# transmission_end_copy-1.net
KiCad netlist of a schematic drawn in EAGLE
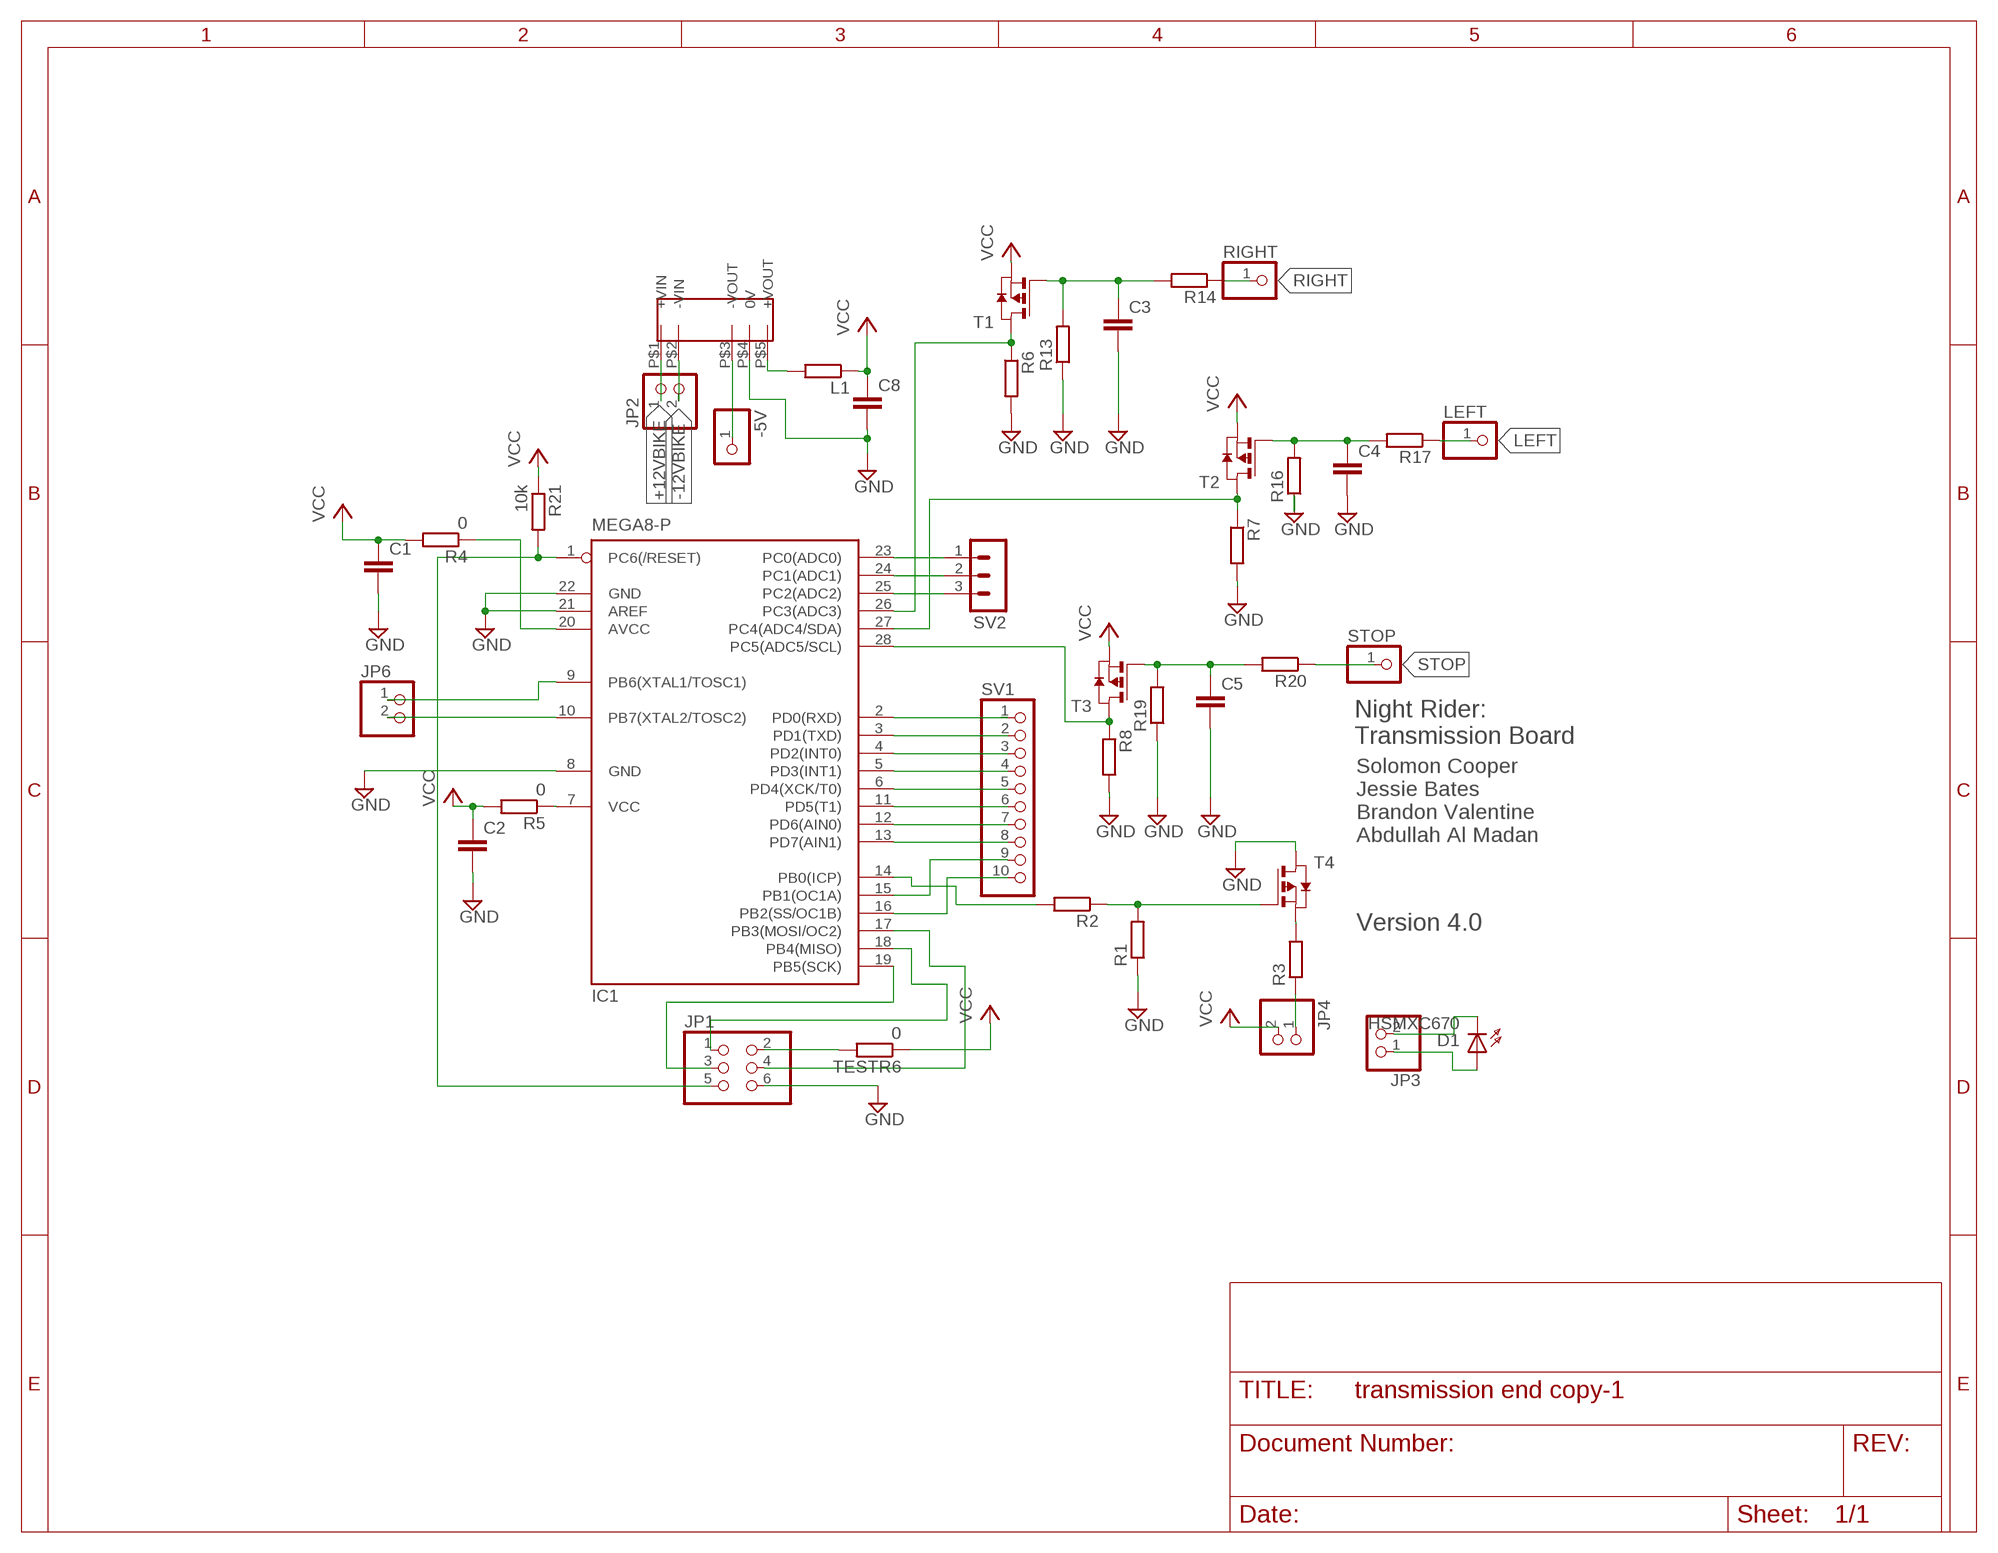
[diagram p0: schematic, sheet 1]

(export (version "E")
  (design (tool "Eeschema 10.0.6"))
  (components
    (comp (ref "-5V")
      (value "PINHD-1X1")
      (footprint "eagle-import:1X01")
      (libsource (lib "eagle-import") (part "PINHD-1X1"))
    )
    (comp (ref "C1")
      (value "C-EUC0805")
      (footprint "eagle-import:C0805")
      (libsource (lib "eagle-import") (part "C-EUC0805"))
    )
    (comp (ref "C2")
      (value "C-EUC0805")
      (footprint "eagle-import:C0805")
      (libsource (lib "eagle-import") (part "C-EUC0805"))
    )
    (comp (ref "C3")
      (value "C-EUC0805")
      (footprint "eagle-import:C0805")
      (libsource (lib "eagle-import") (part "C-EUC0805"))
    )
    (comp (ref "C4")
      (value "C-EUC0805")
      (footprint "eagle-import:C0805")
      (libsource (lib "eagle-import") (part "C-EUC0805"))
    )
    (comp (ref "C5")
      (value "C-EUC0805")
      (footprint "eagle-import:C0805")
      (libsource (lib "eagle-import") (part "C-EUC0805"))
    )
    (comp (ref "C8")
      (value "C-EUC0805")
      (footprint "eagle-import:C0805")
      (libsource (lib "eagle-import") (part "C-EUC0805"))
    )
    (comp (ref "D1")
      (value "HSMXC670")
      (footprint "eagle-import:HSMXC670")
      (fields (field (name "OC_FARNELL") "unknown") (field (name "OC_NEWARK") "unknown"))
      (libsource (lib "eagle-import") (part "HSMXC670"))
    )
    (comp (ref "IC1")
      (value "MEGA8-P")
      (footprint "eagle-import:DIL28-3")
      (libsource (lib "eagle-import") (part "MEGA8-P"))
    )
    (comp (ref "JP1")
      (value "PINHD-2X3")
      (footprint "eagle-import:2X03")
      (libsource (lib "eagle-import") (part "PINHD-2X3"))
    )
    (comp (ref "JP2")
      (value "PINHD-1X2")
      (footprint "eagle-import:1X02")
      (libsource (lib "eagle-import") (part "PINHD-1X2"))
    )
    (comp (ref "JP3")
      (value "PINHD-1X2")
      (footprint "eagle-import:1X02")
      (libsource (lib "eagle-import") (part "PINHD-1X2"))
    )
    (comp (ref "JP4")
      (value "PINHD-1X2")
      (footprint "eagle-import:1X02")
      (libsource (lib "eagle-import") (part "PINHD-1X2"))
    )
    (comp (ref "JP6")
      (value "PINHD-1X2")
      (footprint "eagle-import:1X02")
      (libsource (lib "eagle-import") (part "PINHD-1X2"))
    )
    (comp (ref "L1")
      (value "R-EU_M0805")
      (footprint "eagle-import:M0805")
      (libsource (lib "eagle-import") (part "R-EU_M0805"))
    )
    (comp (ref "LEFT")
      (value "PINHD-1X1")
      (footprint "eagle-import:1X01")
      (libsource (lib "eagle-import") (part "PINHD-1X1"))
    )
    (comp (ref "R1")
      (value "R-EU_M0805")
      (footprint "eagle-import:M0805")
      (libsource (lib "eagle-import") (part "R-EU_M0805"))
    )
    (comp (ref "R2")
      (value "R-EU_M0805")
      (footprint "eagle-import:M0805")
      (libsource (lib "eagle-import") (part "R-EU_M0805"))
    )
    (comp (ref "R3")
      (value "R-EU_M0805")
      (footprint "eagle-import:M0805")
      (libsource (lib "eagle-import") (part "R-EU_M0805"))
    )
    (comp (ref "R4")
      (value "0")
      (footprint "eagle-import:M0805")
      (libsource (lib "eagle-import") (part "R-EU_M0805"))
    )
    (comp (ref "R5")
      (value "0")
      (footprint "eagle-import:M0805")
      (libsource (lib "eagle-import") (part "R-EU_M0805"))
    )
    (comp (ref "R6")
      (value "R-EU_M0805")
      (footprint "eagle-import:M0805")
      (libsource (lib "eagle-import") (part "R-EU_M0805"))
    )
    (comp (ref "R7")
      (value "R-EU_M0805")
      (footprint "eagle-import:M0805")
      (libsource (lib "eagle-import") (part "R-EU_M0805"))
    )
    (comp (ref "R8")
      (value "R-EU_M0805")
      (footprint "eagle-import:M0805")
      (libsource (lib "eagle-import") (part "R-EU_M0805"))
    )
    (comp (ref "R13")
      (value "R-EU_M0805")
      (footprint "eagle-import:M0805")
      (libsource (lib "eagle-import") (part "R-EU_M0805"))
    )
    (comp (ref "R14")
      (value "R-EU_M0805")
      (footprint "eagle-import:M0805")
      (libsource (lib "eagle-import") (part "R-EU_M0805"))
    )
    (comp (ref "R16")
      (value "R-EU_M0805")
      (footprint "eagle-import:M0805")
      (libsource (lib "eagle-import") (part "R-EU_M0805"))
    )
    (comp (ref "R17")
      (value "R-EU_M0805")
      (footprint "eagle-import:M0805")
      (libsource (lib "eagle-import") (part "R-EU_M0805"))
    )
    (comp (ref "R19")
      (value "R-EU_M0805")
      (footprint "eagle-import:M0805")
      (libsource (lib "eagle-import") (part "R-EU_M0805"))
    )
    (comp (ref "R20")
      (value "R-EU_M0805")
      (footprint "eagle-import:M0805")
      (libsource (lib "eagle-import") (part "R-EU_M0805"))
    )
    (comp (ref "R21")
      (value "10k")
      (footprint "eagle-import:M0805")
      (libsource (lib "eagle-import") (part "R-EU_M0805"))
    )
    (comp (ref "RIGHT")
      (value "PINHD-1X1")
      (footprint "eagle-import:1X01")
      (libsource (lib "eagle-import") (part "PINHD-1X1"))
    )
    (comp (ref "STOP")
      (value "PINHD-1X1")
      (footprint "eagle-import:1X01")
      (libsource (lib "eagle-import") (part "PINHD-1X1"))
    )
    (comp (ref "SV1")
      (value "PINHD-1X10")
      (footprint "eagle-import:1X10")
      (libsource (lib "eagle-import") (part "PINHD-1X10"))
    )
    (comp (ref "SV2")
      (value "MA03-1")
      (footprint "eagle-import:MA03-1")
      (libsource (lib "eagle-import") (part "MA03-1"))
    )
    (comp (ref "T1")
      (value "PMOSSOT23")
      (footprint "eagle-import:SOT-23")
      (fields (field (name "OC_FARNELL") "unknown") (field (name "OC_NEWARK") "unknown"))
      (libsource (lib "eagle-import") (part "PMOSSOT23"))
    )
    (comp (ref "T2")
      (value "PMOSSOT23")
      (footprint "eagle-import:SOT-23")
      (libsource (lib "eagle-import") (part "PMOSSOT23"))
    )
    (comp (ref "T3")
      (value "PMOSSOT23")
      (footprint "eagle-import:SOT-23")
      (libsource (lib "eagle-import") (part "PMOSSOT23"))
    )
    (comp (ref "T4")
      (value "PMOSSOT23")
      (footprint "eagle-import:SOT-23")
      (fields (field (name "OC_FARNELL") "unknown") (field (name "OC_NEWARK") "unknown"))
      (libsource (lib "eagle-import") (part "PMOSSOT23"))
    )
    (comp (ref "TESTR6")
      (value "0")
      (footprint "eagle-import:M0805")
      (libsource (lib "eagle-import") (part "R-EU_M0805"))
    )
    (comp (ref "U$1")
      (value "NKA1205SC")
      (footprint "eagle-import:NKA1205SC")
      (libsource (lib "eagle-import") (part "NKA1205SC"))
    )
  )
  (nets
    (net (code "1") (name "+12VBIKE") (class "Default")
      (node (ref "JP2") (pin "1") (pinfunction "1_1") (pintype "passive"))
      (node (ref "U$1") (pin "P$1") (pinfunction "+VIN_P$1") (pintype "bidirectional"))
    )
    (net (code "2") (name "-12VBIKE") (class "Default")
      (node (ref "JP2") (pin "2") (pinfunction "2_2") (pintype "passive"))
      (node (ref "U$1") (pin "P$2") (pinfunction "-VIN_P$2") (pintype "bidirectional"))
    )
    (net (code "3") (name "GND") (class "Default")
      (node (ref "C1") (pin "2") (pinfunction "2_2") (pintype "passive"))
      (node (ref "C2") (pin "2") (pinfunction "2_2") (pintype "passive"))
      (node (ref "C3") (pin "2") (pinfunction "2_2") (pintype "passive"))
      (node (ref "C4") (pin "2") (pinfunction "2_2") (pintype "passive"))
      (node (ref "C5") (pin "2") (pinfunction "2_2") (pintype "passive"))
      (node (ref "C8") (pin "2") (pinfunction "2_2") (pintype "passive"))
      (node (ref "IC1") (pin "21") (pinfunction "AREF_21") (pintype "passive"))
      (node (ref "IC1") (pin "22") (pinfunction "GND_22") (pintype "power_in"))
      (node (ref "IC1") (pin "8") (pinfunction "GND_8") (pintype "power_in"))
      (node (ref "JP1") (pin "6") (pinfunction "6_6") (pintype "passive"))
      (node (ref "R1") (pin "1") (pinfunction "1_1") (pintype "passive"))
      (node (ref "R13") (pin "1") (pinfunction "1_1") (pintype "passive"))
      (node (ref "R16") (pin "1") (pinfunction "1_1") (pintype "passive"))
      (node (ref "R19") (pin "1") (pinfunction "1_1") (pintype "passive"))
      (node (ref "R6") (pin "2") (pinfunction "2_2") (pintype "passive"))
      (node (ref "R7") (pin "2") (pinfunction "2_2") (pintype "passive"))
      (node (ref "R8") (pin "2") (pinfunction "2_2") (pintype "passive"))
      (node (ref "T4") (pin "1") (pinfunction "D_1") (pintype "passive"))
      (node (ref "U$1") (pin "P$4") (pinfunction "0V_P$4") (pintype "bidirectional"))
    )
    (net (code "4") (name "LEFT") (class "Default")
      (node (ref "LEFT") (pin "1") (pinfunction "1_1") (pintype "passive"))
      (node (ref "R17") (pin "1") (pinfunction "1_1") (pintype "passive"))
    )
    (net (code "5") (name "Net-(D1-C)") (class "Default")
      (node (ref "D1") (pin "K") (pinfunction "C_K") (pintype "passive"))
      (node (ref "JP3") (pin "2") (pinfunction "2_2") (pintype "passive"))
    )
    (net (code "6") (name "Net-(D1-PadA)") (class "Default")
      (node (ref "D1") (pin "A") (pinfunction "A_A") (pintype "passive"))
      (node (ref "JP3") (pin "1") (pinfunction "1_1") (pintype "passive"))
    )
    (net (code "7") (name "Net-(IC1-AVCC)") (class "Default")
      (node (ref "IC1") (pin "20") (pinfunction "AVCC_20") (pintype "power_in"))
      (node (ref "R4") (pin "1") (pinfunction "1_1") (pintype "passive"))
    )
    (net (code "8") (name "Net-(IC1-PB0(ICP))") (class "Default")
      (node (ref "IC1") (pin "14") (pinfunction "PB0(ICP)_14") (pintype "bidirectional"))
      (node (ref "R2") (pin "2") (pinfunction "2_2") (pintype "passive"))
    )
    (net (code "9") (name "Net-(IC1-PB1(OC1A))") (class "Default")
      (node (ref "IC1") (pin "15") (pinfunction "PB1(OC1A)_15") (pintype "bidirectional"))
      (node (ref "SV1") (pin "9") (pinfunction "9_9") (pintype "passive"))
    )
    (net (code "10") (name "Net-(IC1-PB2(SS{slash}OC1B))") (class "Default")
      (node (ref "IC1") (pin "16") (pinfunction "PB2(SS/OC1B)_16") (pintype "bidirectional"))
      (node (ref "SV1") (pin "10") (pinfunction "10_10") (pintype "passive"))
    )
    (net (code "11") (name "Net-(IC1-PB3(MOSI{slash}OC2))") (class "Default")
      (node (ref "IC1") (pin "17") (pinfunction "PB3(MOSI/OC2)_17") (pintype "bidirectional"))
      (node (ref "JP1") (pin "4") (pinfunction "4_4") (pintype "passive"))
    )
    (net (code "12") (name "Net-(IC1-PB4(MISO))") (class "Default")
      (node (ref "IC1") (pin "18") (pinfunction "PB4(MISO)_18") (pintype "bidirectional"))
      (node (ref "JP1") (pin "1") (pinfunction "1_1") (pintype "passive"))
    )
    (net (code "13") (name "Net-(IC1-PB5(SCK))") (class "Default")
      (node (ref "IC1") (pin "19") (pinfunction "PB5(SCK)_19") (pintype "bidirectional"))
      (node (ref "JP1") (pin "3") (pinfunction "3_3") (pintype "passive"))
    )
    (net (code "14") (name "Net-(IC1-PB6(XTAL1{slash}TOSC1))") (class "Default")
      (node (ref "IC1") (pin "9") (pinfunction "PB6(XTAL1/TOSC1)_9") (pintype "bidirectional"))
      (node (ref "JP6") (pin "1") (pinfunction "1_1") (pintype "passive"))
    )
    (net (code "15") (name "Net-(IC1-PB7(XTAL2{slash}TOSC2))") (class "Default")
      (node (ref "IC1") (pin "10") (pinfunction "PB7(XTAL2/TOSC2)_10") (pintype "bidirectional"))
      (node (ref "JP6") (pin "2") (pinfunction "2_2") (pintype "passive"))
    )
    (net (code "16") (name "Net-(IC1-PC0(ADC0))") (class "Default")
      (node (ref "IC1") (pin "23") (pinfunction "PC0(ADC0)_23") (pintype "bidirectional"))
      (node (ref "SV2") (pin "1") (pinfunction "1_1") (pintype "passive"))
    )
    (net (code "17") (name "Net-(IC1-PC1(ADC1))") (class "Default")
      (node (ref "IC1") (pin "24") (pinfunction "PC1(ADC1)_24") (pintype "bidirectional"))
      (node (ref "SV2") (pin "2") (pinfunction "2_2") (pintype "passive"))
    )
    (net (code "18") (name "Net-(IC1-PC2(ADC2))") (class "Default")
      (node (ref "IC1") (pin "25") (pinfunction "PC2(ADC2)_25") (pintype "bidirectional"))
      (node (ref "SV2") (pin "3") (pinfunction "3_3") (pintype "passive"))
    )
    (net (code "19") (name "Net-(IC1-PC3(ADC3))") (class "Default")
      (node (ref "IC1") (pin "26") (pinfunction "PC3(ADC3)_26") (pintype "bidirectional"))
      (node (ref "R6") (pin "1") (pinfunction "1_1") (pintype "passive"))
      (node (ref "T1") (pin "1") (pinfunction "D_1") (pintype "passive"))
    )
    (net (code "20") (name "Net-(IC1-PC4(ADC4{slash}SDA))") (class "Default")
      (node (ref "IC1") (pin "27") (pinfunction "PC4(ADC4/SDA)_27") (pintype "bidirectional"))
      (node (ref "R7") (pin "1") (pinfunction "1_1") (pintype "passive"))
      (node (ref "T2") (pin "1") (pinfunction "D_1") (pintype "passive"))
    )
    (net (code "21") (name "Net-(IC1-PC5(ADC5{slash}SCL))") (class "Default")
      (node (ref "IC1") (pin "28") (pinfunction "PC5(ADC5/SCL)_28") (pintype "bidirectional"))
      (node (ref "R8") (pin "1") (pinfunction "1_1") (pintype "passive"))
      (node (ref "T3") (pin "1") (pinfunction "D_1") (pintype "passive"))
    )
    (net (code "22") (name "Net-(IC1-PC6({slash}RESET))") (class "Default")
      (node (ref "IC1") (pin "1") (pinfunction "PC6(/RESET)_1") (pintype "bidirectional"))
      (node (ref "JP1") (pin "5") (pinfunction "5_5") (pintype "passive"))
      (node (ref "R21") (pin "2") (pinfunction "2_2") (pintype "passive"))
    )
    (net (code "23") (name "Net-(IC1-PD0(RXD))") (class "Default")
      (node (ref "IC1") (pin "2") (pinfunction "PD0(RXD)_2") (pintype "bidirectional"))
      (node (ref "SV1") (pin "1") (pinfunction "1_1") (pintype "passive"))
    )
    (net (code "24") (name "Net-(IC1-PD1(TXD))") (class "Default")
      (node (ref "IC1") (pin "3") (pinfunction "PD1(TXD)_3") (pintype "bidirectional"))
      (node (ref "SV1") (pin "2") (pinfunction "2_2") (pintype "passive"))
    )
    (net (code "25") (name "Net-(IC1-PD2(INT0))") (class "Default")
      (node (ref "IC1") (pin "4") (pinfunction "PD2(INT0)_4") (pintype "bidirectional"))
      (node (ref "SV1") (pin "3") (pinfunction "3_3") (pintype "passive"))
    )
    (net (code "26") (name "Net-(IC1-PD3(INT1))") (class "Default")
      (node (ref "IC1") (pin "5") (pinfunction "PD3(INT1)_5") (pintype "bidirectional"))
      (node (ref "SV1") (pin "4") (pinfunction "4_4") (pintype "passive"))
    )
    (net (code "27") (name "Net-(IC1-PD4(XCK{slash}T0))") (class "Default")
      (node (ref "IC1") (pin "6") (pinfunction "PD4(XCK/T0)_6") (pintype "bidirectional"))
      (node (ref "SV1") (pin "5") (pinfunction "5_5") (pintype "passive"))
    )
    (net (code "28") (name "Net-(IC1-PD5(T1))") (class "Default")
      (node (ref "IC1") (pin "11") (pinfunction "PD5(T1)_11") (pintype "bidirectional"))
      (node (ref "SV1") (pin "6") (pinfunction "6_6") (pintype "passive"))
    )
    (net (code "29") (name "Net-(IC1-PD6(AIN0))") (class "Default")
      (node (ref "IC1") (pin "12") (pinfunction "PD6(AIN0)_12") (pintype "bidirectional"))
      (node (ref "SV1") (pin "7") (pinfunction "7_7") (pintype "passive"))
    )
    (net (code "30") (name "Net-(IC1-PD7(AIN1))") (class "Default")
      (node (ref "IC1") (pin "13") (pinfunction "PD7(AIN1)_13") (pintype "bidirectional"))
      (node (ref "SV1") (pin "8") (pinfunction "8_8") (pintype "passive"))
    )
    (net (code "31") (name "Net-(IC1-VCC)") (class "Default")
      (node (ref "IC1") (pin "7") (pinfunction "VCC_7") (pintype "power_in"))
      (node (ref "R5") (pin "1") (pinfunction "1_1") (pintype "passive"))
    )
    (net (code "32") (name "Net-(JP1-Pad2)") (class "Default")
      (node (ref "JP1") (pin "2") (pinfunction "2_2") (pintype "passive"))
      (node (ref "TESTR6") (pin "2") (pinfunction "2_2") (pintype "passive"))
    )
    (net (code "33") (name "Net-(JP4-Pad1)") (class "Default")
      (node (ref "JP4") (pin "1") (pinfunction "1_1") (pintype "passive"))
      (node (ref "R3") (pin "1") (pinfunction "1_1") (pintype "passive"))
    )
    (net (code "34") (name "Net-(T1-G)") (class "Default")
      (node (ref "C3") (pin "1") (pinfunction "1_1") (pintype "passive"))
      (node (ref "R13") (pin "2") (pinfunction "2_2") (pintype "passive"))
      (node (ref "R14") (pin "2") (pinfunction "2_2") (pintype "passive"))
      (node (ref "T1") (pin "3") (pinfunction "G_3") (pintype "passive"))
    )
    (net (code "35") (name "Net-(T2-G)") (class "Default")
      (node (ref "C4") (pin "1") (pinfunction "1_1") (pintype "passive"))
      (node (ref "R16") (pin "2") (pinfunction "2_2") (pintype "passive"))
      (node (ref "R17") (pin "2") (pinfunction "2_2") (pintype "passive"))
      (node (ref "T2") (pin "3") (pinfunction "G_3") (pintype "passive"))
    )
    (net (code "36") (name "Net-(T3-G)") (class "Default")
      (node (ref "C5") (pin "1") (pinfunction "1_1") (pintype "passive"))
      (node (ref "R19") (pin "2") (pinfunction "2_2") (pintype "passive"))
      (node (ref "R20") (pin "2") (pinfunction "2_2") (pintype "passive"))
      (node (ref "T3") (pin "3") (pinfunction "G_3") (pintype "passive"))
    )
    (net (code "37") (name "Net-(T4-G)") (class "Default")
      (node (ref "R1") (pin "2") (pinfunction "2_2") (pintype "passive"))
      (node (ref "R2") (pin "1") (pinfunction "1_1") (pintype "passive"))
      (node (ref "T4") (pin "3") (pinfunction "G_3") (pintype "passive"))
    )
    (net (code "38") (name "Net-(T4-S)") (class "Default")
      (node (ref "R3") (pin "2") (pinfunction "2_2") (pintype "passive"))
      (node (ref "T4") (pin "2") (pinfunction "S_2") (pintype "passive"))
    )
    (net (code "39") (name "Net-(U$1-+VOUT)") (class "Default")
      (node (ref "L1") (pin "2") (pinfunction "2_2") (pintype "passive"))
      (node (ref "U$1") (pin "P$5") (pinfunction "+VOUT_P$5") (pintype "bidirectional"))
    )
    (net (code "40") (name "Net-(U$1--VOUT)") (class "Default")
      (node (ref "-5V") (pin "1") (pinfunction "1_1") (pintype "passive"))
      (node (ref "U$1") (pin "P$3") (pinfunction "-VOUT_P$3") (pintype "bidirectional"))
    )
    (net (code "41") (name "RIGHT") (class "Default")
      (node (ref "R14") (pin "1") (pinfunction "1_1") (pintype "passive"))
      (node (ref "RIGHT") (pin "1") (pinfunction "1_1") (pintype "passive"))
    )
    (net (code "42") (name "STOP") (class "Default")
      (node (ref "R20") (pin "1") (pinfunction "1_1") (pintype "passive"))
      (node (ref "STOP") (pin "1") (pinfunction "1_1") (pintype "passive"))
    )
    (net (code "43") (name "VCC") (class "Default")
      (node (ref "C1") (pin "1") (pinfunction "1_1") (pintype "passive"))
      (node (ref "C2") (pin "1") (pinfunction "1_1") (pintype "passive"))
      (node (ref "C8") (pin "1") (pinfunction "1_1") (pintype "passive"))
      (node (ref "JP4") (pin "2") (pinfunction "2_2") (pintype "passive"))
      (node (ref "L1") (pin "1") (pinfunction "1_1") (pintype "passive"))
      (node (ref "R21") (pin "1") (pinfunction "1_1") (pintype "passive"))
      (node (ref "R4") (pin "2") (pinfunction "2_2") (pintype "passive"))
      (node (ref "R5") (pin "2") (pinfunction "2_2") (pintype "passive"))
      (node (ref "T1") (pin "2") (pinfunction "S_2") (pintype "passive"))
      (node (ref "T2") (pin "2") (pinfunction "S_2") (pintype "passive"))
      (node (ref "T3") (pin "2") (pinfunction "S_2") (pintype "passive"))
      (node (ref "TESTR6") (pin "1") (pinfunction "1_1") (pintype "passive"))
    )
  )
)
